# Sheet1.net
KiCad netlist of a schematic drawn in Altium Designer
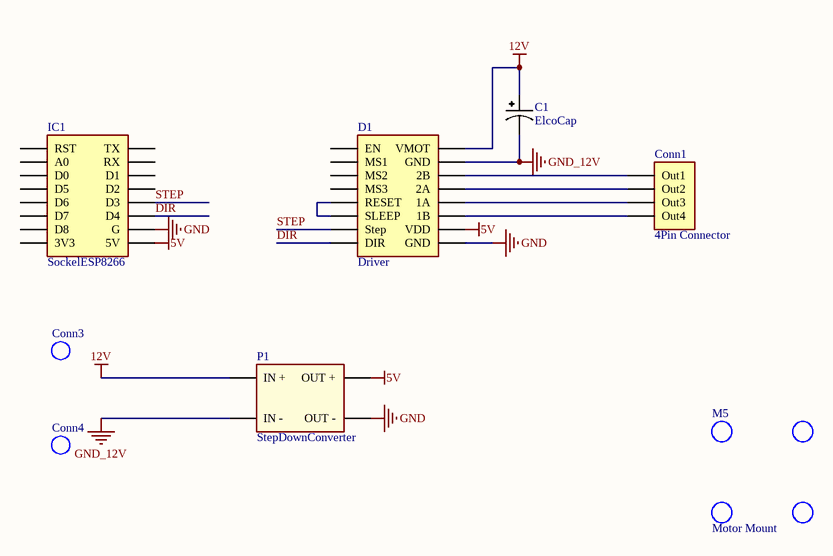
[diagram p0: Sheet1.SchDoc]

(export (version "E")
  (design (tool "Eeschema 10.0.6"))
  (components
    (comp (ref "C1") (value "ElcoCap") (footprint "ElcCap") (libsource (lib "Schlib1") (part "ElcoCap")))
    (comp (ref "Conn1")
      (value "4Pin Connector")
      (footprint "4Pin Connector")
      (libsource (lib "Schlib1") (part "4Pin Connector"))
    )
    (comp (ref "Conn3")
      (value "MountHole")
      (footprint "MountHOle")
      (libsource (lib "Schlib1") (part "MountHole"))
    )
    (comp (ref "Conn4")
      (value "MountHole")
      (footprint "MountHOle")
      (libsource (lib "Schlib1") (part "MountHole"))
    )
    (comp (ref "D1") (value "Driver") (footprint "DiverSockel") (libsource (lib "Schlib1") (part "Driver")))
    (comp (ref "IC1")
      (value "SockelESP8266")
      (footprint "ESP8266 Sockel")
      (description "ESP8266 D1 mini Sockel")
      (libsource (lib "Schlib1") (part "SockelESP8266"))
    )
    (comp (ref "M5")
      (value "Motor Mount")
      (footprint "Motor Mount")
      (libsource (lib "Schlib1") (part "Motor Mount"))
    )
    (comp (ref "P1")
      (value "StepDownConverter")
      (footprint "StepDownConverter")
      (libsource (lib "Schlib1") (part "StepDownConverter"))
    )
  )
  (nets
    (net (code "1") (name "/DIR") (class "Default")
      (node (ref "D1") (pin "8") (pinfunction "DIR_8") (pintype "passive"))
      (node (ref "IC1") (pin "3") (pinfunction "D4_3") (pintype "passive"))
    )
    (net (code "2") (name "/STEP") (class "Default")
      (node (ref "D1") (pin "7") (pinfunction "Step_7") (pintype "passive"))
      (node (ref "IC1") (pin "4") (pinfunction "D3_4") (pintype "passive"))
    )
    (net (code "3") (name "5V") (class "Default")
      (node (ref "D1") (pin "15") (pinfunction "VDD_15") (pintype "passive"))
      (node (ref "IC1") (pin "1") (pinfunction "5V_1") (pintype "passive"))
      (node (ref "P1") (pin "3") (pinfunction "OUT_+_3") (pintype "passive"))
    )
    (net (code "4") (name "12V") (class "Default")
      (node (ref "C1") (pin "1") (pinfunction "P_1") (pintype "passive"))
      (node (ref "D1") (pin "9") (pinfunction "VMOT_9") (pintype "passive"))
      (node (ref "P1") (pin "1") (pinfunction "IN_+_1") (pintype "passive"))
    )
    (net (code "5") (name "GND") (class "Default")
      (node (ref "D1") (pin "16") (pinfunction "GND_16") (pintype "passive"))
      (node (ref "IC1") (pin "2") (pinfunction "G_2") (pintype "passive"))
      (node (ref "P1") (pin "4") (pinfunction "OUT_-_4") (pintype "passive"))
    )
    (net (code "6") (name "GND_12V") (class "Default")
      (node (ref "C1") (pin "2") (pinfunction "N_2") (pintype "passive"))
      (node (ref "D1") (pin "10") (pinfunction "GND_10") (pintype "passive"))
      (node (ref "P1") (pin "2") (pinfunction "IN_-_2") (pintype "passive"))
    )
    (net (code "7") (name "Net-(Conn1-Out1)") (class "Default")
      (node (ref "Conn1") (pin "1") (pinfunction "Out1_1") (pintype "passive"))
      (node (ref "D1") (pin "11") (pinfunction "2B_11") (pintype "passive"))
    )
    (net (code "8") (name "Net-(Conn1-Out2)") (class "Default")
      (node (ref "Conn1") (pin "2") (pinfunction "Out2_2") (pintype "passive"))
      (node (ref "D1") (pin "12") (pinfunction "2A_12") (pintype "passive"))
    )
    (net (code "9") (name "Net-(Conn1-Out3)") (class "Default")
      (node (ref "Conn1") (pin "3") (pinfunction "Out3_3") (pintype "passive"))
      (node (ref "D1") (pin "13") (pinfunction "1A_13") (pintype "passive"))
    )
    (net (code "10") (name "Net-(Conn1-Out4)") (class "Default")
      (node (ref "Conn1") (pin "4") (pinfunction "Out4_4") (pintype "passive"))
      (node (ref "D1") (pin "14") (pinfunction "1B_14") (pintype "passive"))
    )
    (net (code "11") (name "Net-(D1-RESET)") (class "Default")
      (node (ref "D1") (pin "5") (pinfunction "RESET_5") (pintype "passive"))
      (node (ref "D1") (pin "6") (pinfunction "SLEEP_6") (pintype "passive"))
    )
    (net (code "12") (name "unconnected-(D1-EN-Pad1)") (class "Default")
      (node (ref "D1") (pin "1") (pinfunction "EN_1") (pintype "passive"))
    )
    (net (code "13") (name "unconnected-(D1-MS1-Pad2)") (class "Default")
      (node (ref "D1") (pin "2") (pinfunction "MS1_2") (pintype "passive"))
    )
    (net (code "14") (name "unconnected-(D1-MS2-Pad3)") (class "Default")
      (node (ref "D1") (pin "3") (pinfunction "MS2_3") (pintype "passive"))
    )
    (net (code "15") (name "unconnected-(D1-MS3-Pad4)") (class "Default")
      (node (ref "D1") (pin "4") (pinfunction "MS3_4") (pintype "passive"))
    )
    (net (code "16") (name "unconnected-(IC1-3V3-Pad9)") (class "Default")
      (node (ref "IC1") (pin "9") (pinfunction "3V3_9") (pintype "passive"))
    )
    (net (code "17") (name "unconnected-(IC1-A0-Pad15)") (class "Default")
      (node (ref "IC1") (pin "15") (pinfunction "A0_15") (pintype "passive"))
    )
    (net (code "18") (name "unconnected-(IC1-D0-Pad14)") (class "Default")
      (node (ref "IC1") (pin "14") (pinfunction "D0_14") (pintype "passive"))
    )
    (net (code "19") (name "unconnected-(IC1-D1-Pad6)") (class "Default")
      (node (ref "IC1") (pin "6") (pinfunction "D1_6") (pintype "passive"))
    )
    (net (code "20") (name "unconnected-(IC1-D2-Pad5)") (class "Default")
      (node (ref "IC1") (pin "5") (pinfunction "D2_5") (pintype "passive"))
    )
    (net (code "21") (name "unconnected-(IC1-D5-Pad13)") (class "Default")
      (node (ref "IC1") (pin "13") (pinfunction "D5_13") (pintype "passive"))
    )
    (net (code "22") (name "unconnected-(IC1-D6-Pad12)") (class "Default")
      (node (ref "IC1") (pin "12") (pinfunction "D6_12") (pintype "passive"))
    )
    (net (code "23") (name "unconnected-(IC1-D7-Pad11)") (class "Default")
      (node (ref "IC1") (pin "11") (pinfunction "D7_11") (pintype "passive"))
    )
    (net (code "24") (name "unconnected-(IC1-D8-Pad10)") (class "Default")
      (node (ref "IC1") (pin "10") (pinfunction "D8_10") (pintype "passive"))
    )
    (net (code "25") (name "unconnected-(IC1-RST-Pad16)") (class "Default")
      (node (ref "IC1") (pin "16") (pinfunction "RST_16") (pintype "passive"))
    )
    (net (code "26") (name "unconnected-(IC1-RX-Pad7)") (class "Default")
      (node (ref "IC1") (pin "7") (pinfunction "RX_7") (pintype "passive"))
    )
    (net (code "27") (name "unconnected-(IC1-TX-Pad8)") (class "Default")
      (node (ref "IC1") (pin "8") (pinfunction "TX_8") (pintype "passive"))
    )
  )
)
